# Reader_nano.net
KiCad netlist of a schematic drawn in EAGLE
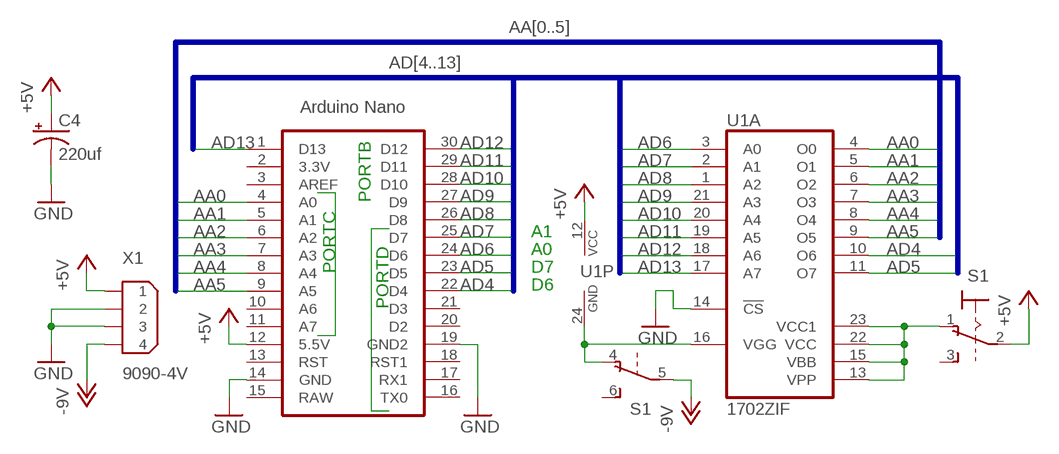
[diagram p0: schematic, sheet 1]

(export (version "E")
  (design (tool "Eeschema 10.0.6"))
  (components
    (comp (ref "C4")
      (value "220uf")
      (footprint "eagle-import:E5-10,5")
      (libsource (lib "eagle-import") (part "CPOL-USE5-10.5"))
    )
    (comp (ref "S1")
      (value "320-938")
      (footprint "eagle-import:320-938")
      (libsource (lib "eagle-import") (part "320-938"))
    )
    (comp (ref "U$1")
      (value "NANO")
      (footprint "eagle-import:NANO")
      (libsource (lib "eagle-import") (part "NANO"))
    )
    (comp (ref "U1")
      (value "1702ZIF")
      (footprint "eagle-import:ZIF24")
      (libsource (lib "eagle-import") (part "1702ZIF"))
    )
    (comp (ref "X1")
      (value "9090-4V")
      (footprint "eagle-import:9090-4V")
      (libsource (lib "eagle-import") (part "9090-4V"))
    )
  )
  (nets
    (net (code "1") (name "+5V") (class "Default")
      (node (ref "C4") (pin "+") (pinfunction "+_+") (pintype "passive"))
      (node (ref "S1") (pin "2") (pinfunction "P_2") (pintype "passive"))
      (node (ref "U$1") (pin "12") (pinfunction "5.5V_12") (pintype "bidirectional"))
      (node (ref "U1") (pin "12") (pinfunction "VCC_12") (pintype "power_in"))
      (node (ref "X1") (pin "1") (pinfunction "1_1") (pintype "passive"))
    )
    (net (code "2") (name "-9V") (class "Default")
      (node (ref "S1") (pin "5") (pinfunction "P_5") (pintype "passive"))
      (node (ref "X1") (pin "4") (pinfunction "4_4") (pintype "passive"))
    )
    (net (code "3") (name "/AA0") (class "Default")
      (node (ref "U$1") (pin "4") (pinfunction "A0_4") (pintype "bidirectional"))
      (node (ref "U1") (pin "4") (pinfunction "O0_4") (pintype "tri_state"))
    )
    (net (code "4") (name "/AA1") (class "Default")
      (node (ref "U$1") (pin "5") (pinfunction "A1_5") (pintype "bidirectional"))
      (node (ref "U1") (pin "5") (pinfunction "O1_5") (pintype "tri_state"))
    )
    (net (code "5") (name "/AA2") (class "Default")
      (node (ref "U$1") (pin "6") (pinfunction "A2_6") (pintype "bidirectional"))
      (node (ref "U1") (pin "6") (pinfunction "O2_6") (pintype "tri_state"))
    )
    (net (code "6") (name "/AA3") (class "Default")
      (node (ref "U$1") (pin "7") (pinfunction "A3_7") (pintype "bidirectional"))
      (node (ref "U1") (pin "7") (pinfunction "O3_7") (pintype "tri_state"))
    )
    (net (code "7") (name "/AA4") (class "Default")
      (node (ref "U$1") (pin "8") (pinfunction "A4_8") (pintype "bidirectional"))
      (node (ref "U1") (pin "8") (pinfunction "O4_8") (pintype "tri_state"))
    )
    (net (code "8") (name "/AA5") (class "Default")
      (node (ref "U$1") (pin "9") (pinfunction "A5_9") (pintype "bidirectional"))
      (node (ref "U1") (pin "9") (pinfunction "O5_9") (pintype "tri_state"))
    )
    (net (code "10") (name "/AD4") (class "Default")
      (node (ref "U$1") (pin "22") (pinfunction "D4_22") (pintype "bidirectional"))
      (node (ref "U1") (pin "10") (pinfunction "O6_10") (pintype "tri_state"))
    )
    (net (code "11") (name "/AD5") (class "Default")
      (node (ref "U$1") (pin "23") (pinfunction "D5_23") (pintype "bidirectional"))
      (node (ref "U1") (pin "11") (pinfunction "O7_11") (pintype "tri_state"))
    )
    (net (code "12") (name "/AD6") (class "Default")
      (node (ref "U$1") (pin "24") (pinfunction "D6_24") (pintype "bidirectional"))
      (node (ref "U1") (pin "3") (pinfunction "A0_3") (pintype "input"))
    )
    (net (code "13") (name "/AD7") (class "Default")
      (node (ref "U$1") (pin "25") (pinfunction "D7_25") (pintype "bidirectional"))
      (node (ref "U1") (pin "2") (pinfunction "A1_2") (pintype "input"))
    )
    (net (code "14") (name "/AD8") (class "Default")
      (node (ref "U$1") (pin "26") (pinfunction "D8_26") (pintype "bidirectional"))
      (node (ref "U1") (pin "1") (pinfunction "A2_1") (pintype "input"))
    )
    (net (code "15") (name "/AD9") (class "Default")
      (node (ref "U$1") (pin "27") (pinfunction "D9_27") (pintype "bidirectional"))
      (node (ref "U1") (pin "21") (pinfunction "A3_21") (pintype "input"))
    )
    (net (code "16") (name "/AD10") (class "Default")
      (node (ref "U$1") (pin "28") (pinfunction "D10_28") (pintype "bidirectional"))
      (node (ref "U1") (pin "20") (pinfunction "A4_20") (pintype "input"))
    )
    (net (code "17") (name "/AD11") (class "Default")
      (node (ref "U$1") (pin "29") (pinfunction "D11_29") (pintype "bidirectional"))
      (node (ref "U1") (pin "19") (pinfunction "A5_19") (pintype "input"))
    )
    (net (code "18") (name "/AD12") (class "Default")
      (node (ref "U$1") (pin "30") (pinfunction "D12_30") (pintype "bidirectional"))
      (node (ref "U1") (pin "18") (pinfunction "A6_18") (pintype "input"))
    )
    (net (code "19") (name "/AD13") (class "Default")
      (node (ref "U$1") (pin "1") (pinfunction "D13_1") (pintype "bidirectional"))
      (node (ref "U1") (pin "17") (pinfunction "A7_17") (pintype "input"))
    )
    (net (code "21") (name "GND") (class "Default")
      (node (ref "C4") (pin "-") (pinfunction "-_-") (pintype "passive"))
      (node (ref "U$1") (pin "14") (pinfunction "GND_14") (pintype "bidirectional"))
      (node (ref "U$1") (pin "19") (pinfunction "GND2_19") (pintype "bidirectional"))
      (node (ref "U1") (pin "14") (pinfunction "~{CS}_14") (pintype "input"))
      (node (ref "X1") (pin "2") (pinfunction "2_2") (pintype "passive"))
      (node (ref "X1") (pin "3") (pinfunction "3_3") (pintype "passive"))
    )
    (net (code "22") (name "Net-(S1A-O)") (class "Default")
      (node (ref "S1") (pin "1") (pinfunction "O_1") (pintype "passive"))
      (node (ref "U1") (pin "13") (pinfunction "VPP_13") (pintype "input"))
      (node (ref "U1") (pin "15") (pinfunction "VBB_15") (pintype "input"))
      (node (ref "U1") (pin "22") (pinfunction "VCC_22") (pintype "input"))
      (node (ref "U1") (pin "23") (pinfunction "VCC1_23") (pintype "input"))
    )
    (net (code "23") (name "Net-(S1B-O)") (class "Default")
      (node (ref "S1") (pin "4") (pinfunction "O_4") (pintype "passive"))
      (node (ref "U1") (pin "16") (pinfunction "VGG_16") (pintype "input"))
      (node (ref "U1") (pin "24") (pinfunction "GND_24") (pintype "power_in"))
    )
    (net (code "24") (name "unconnected-(S1A-S-Pad3)") (class "Default")
      (node (ref "S1") (pin "3") (pinfunction "S_3") (pintype "passive"))
    )
    (net (code "25") (name "unconnected-(S1B-S-Pad6)") (class "Default")
      (node (ref "S1") (pin "6") (pinfunction "S_6") (pintype "passive"))
    )
    (net (code "26") (name "unconnected-(U$1-3.3V-Pad2)") (class "Default")
      (node (ref "U$1") (pin "2") (pinfunction "3.3V_2") (pintype "bidirectional"))
    )
    (net (code "27") (name "unconnected-(U$1-A6-Pad10)") (class "Default")
      (node (ref "U$1") (pin "10") (pinfunction "A6_10") (pintype "bidirectional"))
    )
    (net (code "28") (name "unconnected-(U$1-A7-Pad11)") (class "Default")
      (node (ref "U$1") (pin "11") (pinfunction "A7_11") (pintype "bidirectional"))
    )
    (net (code "29") (name "unconnected-(U$1-AREF-Pad3)") (class "Default")
      (node (ref "U$1") (pin "3") (pinfunction "AREF_3") (pintype "bidirectional"))
    )
    (net (code "30") (name "unconnected-(U$1-D2-Pad20)") (class "Default")
      (node (ref "U$1") (pin "20") (pinfunction "D2_20") (pintype "bidirectional"))
    )
    (net (code "31") (name "unconnected-(U$1-D3-Pad21)") (class "Default")
      (node (ref "U$1") (pin "21") (pinfunction "D3_21") (pintype "bidirectional"))
    )
    (net (code "32") (name "unconnected-(U$1-RAW-Pad15)") (class "Default")
      (node (ref "U$1") (pin "15") (pinfunction "RAW_15") (pintype "bidirectional"))
    )
    (net (code "33") (name "unconnected-(U$1-RST-Pad13)") (class "Default")
      (node (ref "U$1") (pin "13") (pinfunction "RST_13") (pintype "bidirectional"))
    )
    (net (code "34") (name "unconnected-(U$1-RST1-Pad18)") (class "Default")
      (node (ref "U$1") (pin "18") (pinfunction "RST1_18") (pintype "bidirectional"))
    )
    (net (code "35") (name "unconnected-(U$1-RX1-Pad17)") (class "Default")
      (node (ref "U$1") (pin "17") (pinfunction "RX1_17") (pintype "bidirectional"))
    )
    (net (code "36") (name "unconnected-(U$1-TX0-Pad16)") (class "Default")
      (node (ref "U$1") (pin "16") (pinfunction "TX0_16") (pintype "bidirectional"))
    )
  )
)
